# akkuvizsg_l.net
KiCad netlist of a schematic drawn in EAGLE
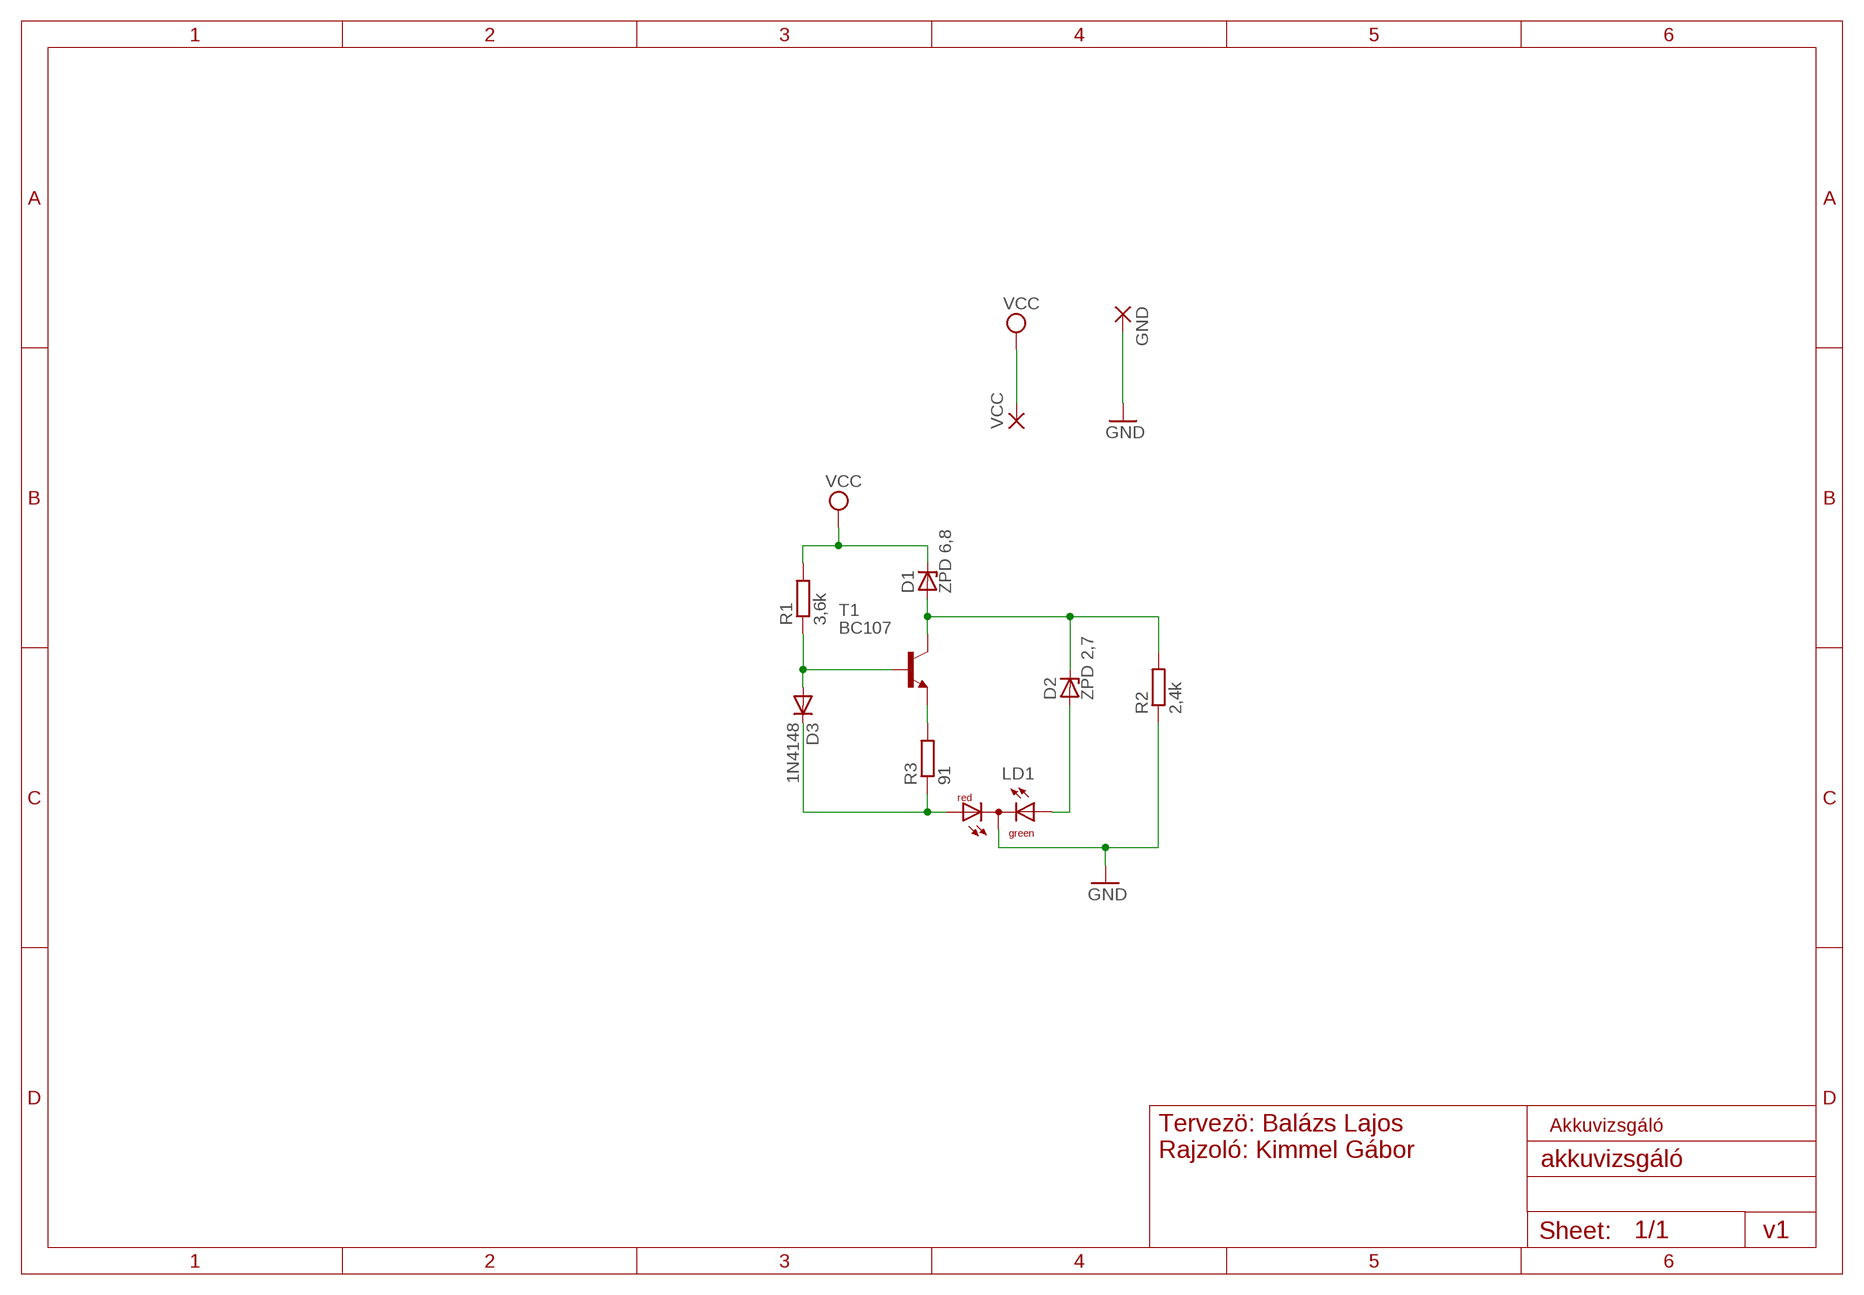
[diagram p0: schematic, sheet 1]

(export (version "E")
  (design (tool "Eeschema 10.0.6"))
  (components
    (comp (ref "D1")
      (value "ZPD 6,8")
      (footprint "eagle-import:DO35Z10")
      (libsource (lib "eagle-import") (part "ZPD"))
    )
    (comp (ref "D2")
      (value "ZPD 2,7")
      (footprint "eagle-import:DO35Z10")
      (libsource (lib "eagle-import") (part "ZPD"))
    )
    (comp (ref "D3")
      (value "1N4148")
      (footprint "eagle-import:DO35-10")
      (libsource (lib "eagle-import") (part "1N4148DO35-10"))
    )
    (comp (ref "GND")
      (value "2,15/1,0")
      (footprint "eagle-import:2,15_1,0")
      (libsource (lib "eagle-import") (part "2,15/1,0"))
    )
    (comp (ref "LD1")
      (value "DUOLED-RG-C")
      (footprint "eagle-import:DUOLED-C-5MM")
      (libsource (lib "eagle-import") (part "DUOLED-RG-C"))
    )
    (comp (ref "R1")
      (value "3,6k")
      (footprint "eagle-import:0204_7")
      (libsource (lib "eagle-import") (part "R-EU_0204/7"))
    )
    (comp (ref "R2")
      (value "2,4k")
      (footprint "eagle-import:0204_7")
      (libsource (lib "eagle-import") (part "R-EU_0204/7"))
    )
    (comp (ref "R3")
      (value "91")
      (footprint "eagle-import:0204_7")
      (libsource (lib "eagle-import") (part "R-EU_0204/7"))
    )
    (comp (ref "T1")
      (value "BC107")
      (footprint "eagle-import:TO18")
      (libsource (lib "eagle-import") (part "BC107"))
    )
    (comp (ref "VCC")
      (value "2,15/1,0")
      (footprint "eagle-import:2,15_1,0")
      (libsource (lib "eagle-import") (part "2,15/1,0"))
    )
  )
  (nets
    (net (code "1") (name "GND") (class "Default")
      (node (ref "GND") (pin "1") (pinfunction "P_1") (pintype "passive"))
      (node (ref "LD1") (pin "C") (pinfunction "C_C") (pintype "passive"))
      (node (ref "R2") (pin "1") (pinfunction "1_1") (pintype "passive"))
    )
    (net (code "2") (name "Net-(D3-PadC)") (class "Default")
      (node (ref "D3") (pin "C") (pinfunction "C_C") (pintype "passive"))
      (node (ref "LD1") (pin "AR") (pinfunction "AR_AR") (pintype "passive"))
      (node (ref "R3") (pin "1") (pinfunction "1_1") (pintype "passive"))
    )
    (net (code "3") (name "Net-(LD1-AG)") (class "Default")
      (node (ref "D2") (pin "A") (pinfunction "A_A") (pintype "passive"))
      (node (ref "LD1") (pin "AX") (pinfunction "AG_AX") (pintype "passive"))
    )
    (net (code "4") (name "Net-(T1-B)") (class "Default")
      (node (ref "D3") (pin "A") (pinfunction "A_A") (pintype "passive"))
      (node (ref "R1") (pin "1") (pinfunction "1_1") (pintype "passive"))
      (node (ref "T1") (pin "2") (pinfunction "B_2") (pintype "passive"))
    )
    (net (code "5") (name "Net-(T1-C)") (class "Default")
      (node (ref "D1") (pin "A") (pinfunction "A_A") (pintype "passive"))
      (node (ref "D2") (pin "C") (pinfunction "C_C") (pintype "passive"))
      (node (ref "R2") (pin "2") (pinfunction "2_2") (pintype "passive"))
      (node (ref "T1") (pin "3") (pinfunction "C_3") (pintype "passive"))
    )
    (net (code "6") (name "Net-(T1-E)") (class "Default")
      (node (ref "R3") (pin "2") (pinfunction "2_2") (pintype "passive"))
      (node (ref "T1") (pin "1") (pinfunction "E_1") (pintype "passive"))
    )
    (net (code "7") (name "VCC") (class "Default")
      (node (ref "D1") (pin "C") (pinfunction "C_C") (pintype "passive"))
      (node (ref "R1") (pin "2") (pinfunction "2_2") (pintype "passive"))
      (node (ref "VCC") (pin "1") (pinfunction "P_1") (pintype "passive"))
    )
  )
)
